# B_Card.net
KiCad netlist of a schematic drawn in Altium Designer
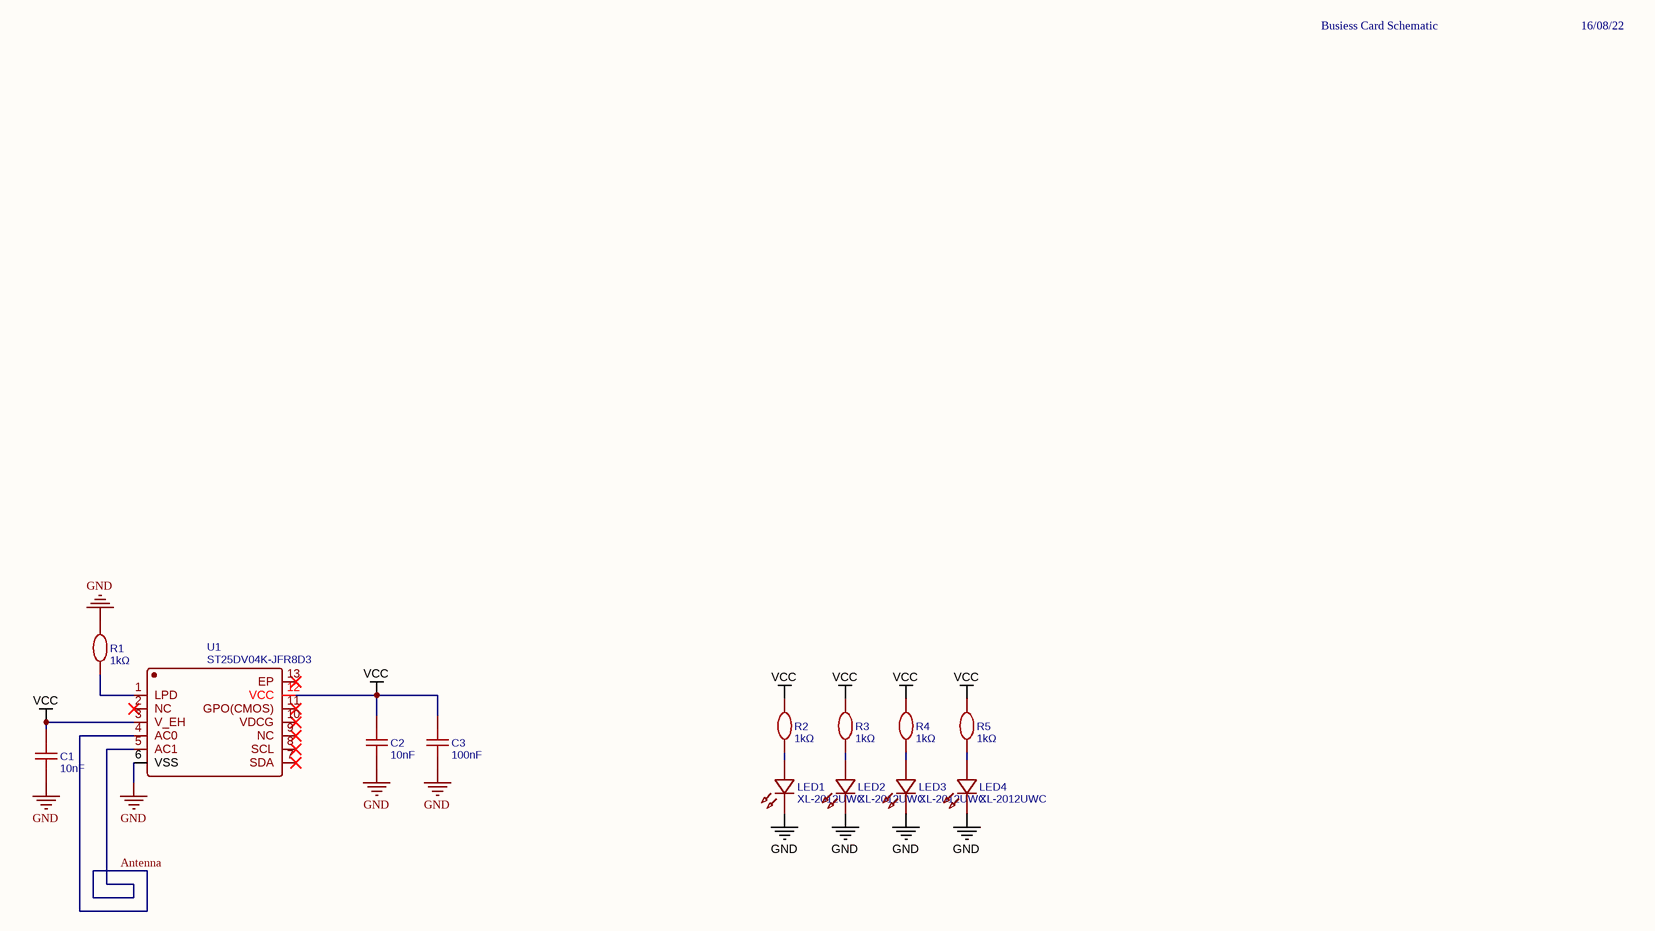
[diagram p0: B_Card.SchDoc]

(export (version "E")
  (design (tool "Eeschema 10.0.6"))
  (components
    (comp (ref "C1")
      (value "10nF")
      (footprint "C0603")
      (fields
        (field (name "BOM_MANUFACTURER PART") "GRM1885C1H103JA01D")
        (field (name "BOM_SUPPLIER PART") "C85973")
      )
      (libsource (lib "altium-import") (part "root_1_10nF_"))
    )
    (comp (ref "C2")
      (value "10nF")
      (footprint "C0603")
      (fields
        (field (name "BOM_MANUFACTURER PART") "GRM1885C1H103JA01D")
        (field (name "BOM_SUPPLIER PART") "C85973")
      )
      (libsource (lib "altium-import") (part "root_3_10nF_"))
    )
    (comp (ref "C3")
      (value "100nF")
      (footprint "C0603")
      (fields
        (field (name "BOM_MANUFACTURER PART") "GRM188R71E104KA01D")
        (field (name "BOM_SUPPLIER PART") "C77050")
      )
      (libsource (lib "altium-import") (part "root_1_100nF_"))
    )
    (comp (ref "LED1")
      (value "XL-2012UWC")
      (footprint "LED0805-RD_WHITE")
      (fields (field (name "BOM_SUPPLIER PART") "C965818") (field (name "CONTRIBUTOR") "LCSC"))
      (libsource (lib "altium-import") (part "root_1_XL-2012UWC_"))
    )
    (comp (ref "LED2")
      (value "XL-2012UWC")
      (footprint "LED0805-RD_WHITE")
      (fields (field (name "BOM_SUPPLIER PART") "C965818") (field (name "CONTRIBUTOR") "LCSC"))
      (libsource (lib "altium-import") (part "root_1_XL-2012UWC_"))
    )
    (comp (ref "LED3")
      (value "XL-2012UWC")
      (footprint "LED0805-RD_WHITE")
      (fields (field (name "BOM_SUPPLIER PART") "C965818") (field (name "CONTRIBUTOR") "LCSC"))
      (libsource (lib "altium-import") (part "root_1_XL-2012UWC_"))
    )
    (comp (ref "LED4")
      (value "XL-2012UWC")
      (footprint "LED0805-RD_WHITE")
      (fields (field (name "BOM_SUPPLIER PART") "C965818") (field (name "CONTRIBUTOR") "LCSC"))
      (libsource (lib "altium-import") (part "root_1_XL-2012UWC_"))
    )
    (comp (ref "R1")
      (value "1kΩ")
      (footprint "R0603")
      (fields
        (field (name "BOM_SUPPLIER PART") "C2907113")
        (field (name "BOM_MANUFACTURER PART") "FRC0603J102 TS")
        (field (name "CONTRIBUTOR") "lcsc")
      )
      (libsource (lib "altium-import") (part "root_1_1kΩ_"))
    )
    (comp (ref "R2")
      (value "1kΩ")
      (footprint "R0603")
      (fields
        (field (name "BOM_SUPPLIER PART") "C2907113")
        (field (name "BOM_MANUFACTURER PART") "FRC0603J102 TS")
        (field (name "CONTRIBUTOR") "lcsc")
      )
      (libsource (lib "altium-import") (part "root_1_1kΩ_"))
    )
    (comp (ref "R3")
      (value "1kΩ")
      (footprint "R0603")
      (fields
        (field (name "BOM_SUPPLIER PART") "C2907113")
        (field (name "BOM_MANUFACTURER PART") "FRC0603J102 TS")
        (field (name "CONTRIBUTOR") "lcsc")
      )
      (libsource (lib "altium-import") (part "root_1_1kΩ_"))
    )
    (comp (ref "R4")
      (value "1kΩ")
      (footprint "R0603")
      (fields
        (field (name "BOM_SUPPLIER PART") "C2907113")
        (field (name "BOM_MANUFACTURER PART") "FRC0603J102 TS")
        (field (name "CONTRIBUTOR") "lcsc")
      )
      (libsource (lib "altium-import") (part "root_1_1kΩ_"))
    )
    (comp (ref "R5")
      (value "1kΩ")
      (footprint "R0603")
      (fields
        (field (name "BOM_SUPPLIER PART") "C2907113")
        (field (name "BOM_MANUFACTURER PART") "FRC0603J102 TS")
        (field (name "CONTRIBUTOR") "lcsc")
      )
      (libsource (lib "altium-import") (part "root_1_1kΩ_"))
    )
    (comp (ref "U1")
      (value "ST25DV04K-JFR8D3")
      (footprint "UDFN-12_L3.0-W3.0-P0.50-BL-EP")
      (fields (field (name "BOM_SUPPLIER PART") "C2654867") (field (name "CONTRIBUTOR") "LCSC"))
      (libsource (lib "altium-import") (part "root_0_ST25DV04K-JFR8D3_"))
    )
  )
  (nets
    (net (code "1") (name "/Antenna") (class "Default")
      (node (ref "U1") (pin "4") (pinfunction "AC0_4") (pintype "passive"))
      (node (ref "U1") (pin "5") (pinfunction "AC1_5") (pintype "passive"))
    )
    (net (code "2") (name "GND") (class "Default")
      (node (ref "C1") (pin "1") (pinfunction "1_1") (pintype "passive"))
      (node (ref "C2") (pin "2") (pinfunction "2_2") (pintype "passive"))
      (node (ref "C3") (pin "1") (pinfunction "1_1") (pintype "passive"))
      (node (ref "LED1") (pin "1") (pinfunction "K_1") (pintype "passive"))
      (node (ref "LED2") (pin "1") (pinfunction "K_1") (pintype "passive"))
      (node (ref "LED3") (pin "1") (pinfunction "K_1") (pintype "passive"))
      (node (ref "LED4") (pin "1") (pinfunction "K_1") (pintype "passive"))
      (node (ref "R1") (pin "2") (pinfunction "2_2") (pintype "passive"))
      (node (ref "U1") (pin "6") (pinfunction "VSS_6") (pintype "passive"))
    )
    (net (code "3") (name "Net-(LED1-A)") (class "Default")
      (node (ref "LED1") (pin "2") (pinfunction "A_2") (pintype "passive"))
      (node (ref "R2") (pin "1") (pinfunction "1_1") (pintype "passive"))
    )
    (net (code "4") (name "Net-(LED2-A)") (class "Default")
      (node (ref "LED2") (pin "2") (pinfunction "A_2") (pintype "passive"))
      (node (ref "R3") (pin "1") (pinfunction "1_1") (pintype "passive"))
    )
    (net (code "5") (name "Net-(LED3-A)") (class "Default")
      (node (ref "LED3") (pin "2") (pinfunction "A_2") (pintype "passive"))
      (node (ref "R4") (pin "1") (pinfunction "1_1") (pintype "passive"))
    )
    (net (code "6") (name "Net-(LED4-A)") (class "Default")
      (node (ref "LED4") (pin "2") (pinfunction "A_2") (pintype "passive"))
      (node (ref "R5") (pin "1") (pinfunction "1_1") (pintype "passive"))
    )
    (net (code "7") (name "Net-(U1-LPD)") (class "Default")
      (node (ref "R1") (pin "1") (pinfunction "1_1") (pintype "passive"))
      (node (ref "U1") (pin "1") (pinfunction "LPD_1") (pintype "passive"))
    )
    (net (code "8") (name "VCC") (class "Default")
      (node (ref "C1") (pin "2") (pinfunction "2_2") (pintype "passive"))
      (node (ref "C2") (pin "1") (pinfunction "1_1") (pintype "passive"))
      (node (ref "C3") (pin "2") (pinfunction "2_2") (pintype "passive"))
      (node (ref "R2") (pin "2") (pinfunction "2_2") (pintype "passive"))
      (node (ref "R3") (pin "2") (pinfunction "2_2") (pintype "passive"))
      (node (ref "R4") (pin "2") (pinfunction "2_2") (pintype "passive"))
      (node (ref "R5") (pin "2") (pinfunction "2_2") (pintype "passive"))
      (node (ref "U1") (pin "12") (pinfunction "VCC_12") (pintype "passive"))
      (node (ref "U1") (pin "3") (pinfunction "V_EH_3") (pintype "passive"))
    )
    (net (code "9") (name "unconnected-(U1-EP-Pad13)") (class "Default")
      (node (ref "U1") (pin "13") (pinfunction "EP_13") (pintype "passive+no_connect"))
    )
    (net (code "10") (name "unconnected-(U1-GPO(CMOS)-Pad11)") (class "Default")
      (node (ref "U1") (pin "11") (pinfunction "GPO(CMOS)_11") (pintype "passive+no_connect"))
    )
    (net (code "11") (name "unconnected-(U1-NC-Pad2)") (class "Default")
      (node (ref "U1") (pin "2") (pinfunction "NC_2") (pintype "passive+no_connect"))
    )
    (net (code "12") (name "unconnected-(U1-NC-Pad9)") (class "Default")
      (node (ref "U1") (pin "9") (pinfunction "NC_9") (pintype "passive+no_connect"))
    )
    (net (code "13") (name "unconnected-(U1-SCL-Pad8)") (class "Default")
      (node (ref "U1") (pin "8") (pinfunction "SCL_8") (pintype "passive+no_connect"))
    )
    (net (code "14") (name "unconnected-(U1-SDA-Pad7)") (class "Default")
      (node (ref "U1") (pin "7") (pinfunction "SDA_7") (pintype "passive+no_connect"))
    )
    (net (code "15") (name "unconnected-(U1-VDCG-Pad10)") (class "Default")
      (node (ref "U1") (pin "10") (pinfunction "VDCG_10") (pintype "passive+no_connect"))
    )
  )
)
